# Cameras.net
KiCad netlist of a schematic drawn in Altium Designer
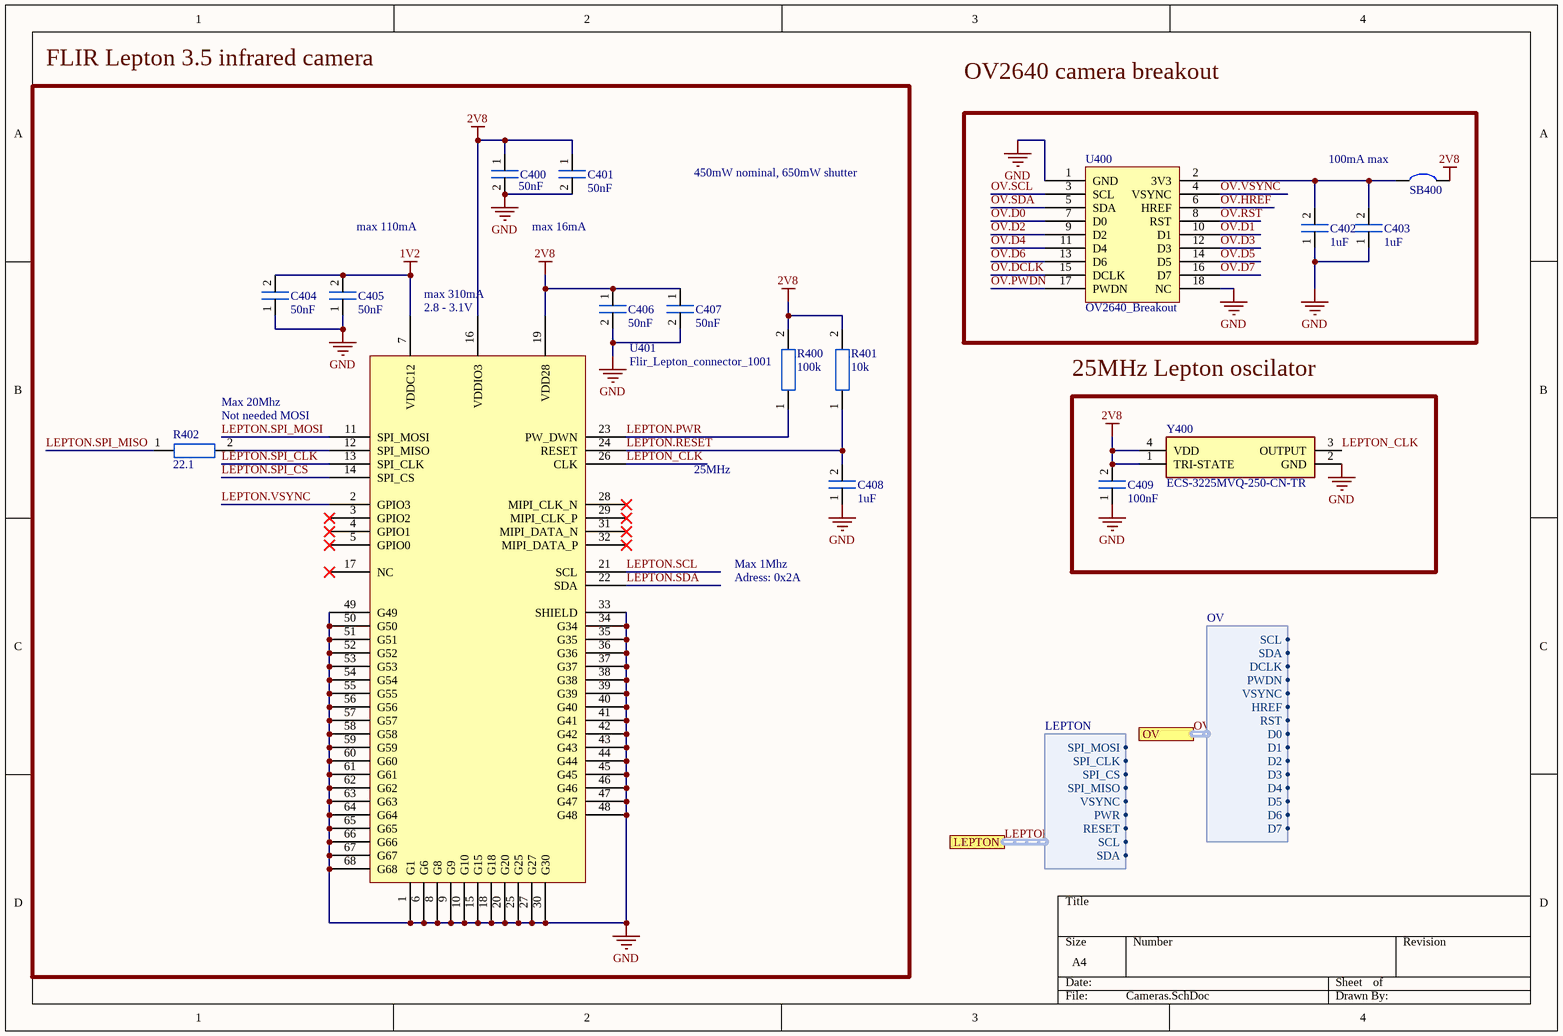
[diagram p0: Cameras.SchDoc]

(export (version "E")
  (design (tool "Eeschema 10.0.6"))
  (components
    (comp (ref "C400")
      (value "50nF")
      (footprint "0402_footprint")
      (description "0402 capacitor")
      (libsource (lib "Schlib1") (part "Capacitor_0402"))
    )
    (comp (ref "C401")
      (value "50nF")
      (footprint "0402_footprint")
      (description "0402 capacitor")
      (libsource (lib "Schlib1") (part "Capacitor_0402"))
    )
    (comp (ref "C402")
      (value "1uF")
      (footprint "0402_footprint")
      (description "0402 capacitor")
      (libsource (lib "Schlib1") (part "Capacitor_0402"))
    )
    (comp (ref "C403")
      (value "1uF")
      (footprint "0402_footprint")
      (description "0402 capacitor")
      (libsource (lib "Schlib1") (part "Capacitor_0402"))
    )
    (comp (ref "C404")
      (value "50nF")
      (footprint "0402_footprint")
      (description "0402 capacitor")
      (libsource (lib "Schlib1") (part "Capacitor_0402"))
    )
    (comp (ref "C405")
      (value "50nF")
      (footprint "0402_footprint")
      (description "0402 capacitor")
      (libsource (lib "Schlib1") (part "Capacitor_0402"))
    )
    (comp (ref "C406")
      (value "50nF")
      (footprint "0402_footprint")
      (description "0402 capacitor")
      (libsource (lib "Schlib1") (part "Capacitor_0402"))
    )
    (comp (ref "C407")
      (value "50nF")
      (footprint "0402_footprint")
      (description "0402 capacitor")
      (libsource (lib "Schlib1") (part "Capacitor_0402"))
    )
    (comp (ref "C408")
      (value "1uF")
      (footprint "0402_footprint")
      (description "0402 capacitor")
      (libsource (lib "Schlib1") (part "Capacitor_0402"))
    )
    (comp (ref "C409")
      (value "100nF")
      (footprint "0402_footprint")
      (description "0402 capacitor")
      (libsource (lib "Schlib1") (part "Capacitor_0402"))
    )
    (comp (ref "R400")
      (value "100k")
      (footprint "0402_footprint")
      (description "0402 resistor")
      (libsource (lib "Schlib1") (part "Resistor_0402"))
    )
    (comp (ref "R401")
      (value "10k")
      (footprint "0402_footprint")
      (description "0402 resistor")
      (libsource (lib "Schlib1") (part "Resistor_0402"))
    )
    (comp (ref "R402")
      (value "22.1")
      (footprint "0402_footprint")
      (description "0402 resistor")
      (libsource (lib "Schlib1") (part "Resistor_0402"))
    )
    (comp (ref "SB400")
      (value "Solder_bridge")
      (footprint "SOLDER_BRIDGE")
      (libsource (lib "Schlib1") (part "Solder_bridge"))
    )
    (comp (ref "U400")
      (value "OV2640_Breakout")
      (footprint "OV2640_BREAKOUT")
      (description "https://www.uctronics.com/download/cam_module/OV2640DS.pdf")
      (libsource (lib "Schlib1") (part "OV2640_Breakout"))
    )
    (comp (ref "U401")
      (value "Flir_Lepton_connector_1001")
      (footprint "105028-1001")
      (libsource (lib "Schlib1") (part "Flir_Lepton_connector_1001"))
    )
    (comp (ref "Y400")
      (value "ECS-3225MVQ-250-CN-TR")
      (footprint "SamacSys:ECS3225MVQ250CNTR")
      (description "25MHz oscilattor")
      (fields (field (name "MOUSER PART NUMBER") "520-3225MVQ-250-CN-T"))
      (libsource (lib "*") (part "ECS-3225MVQ-250-CN-TR"))
    )
  )
  (nets
    (net (code "3") (name "/LEPTON.PWR") (class "Default")
      (node (ref "R400") (pin "1") (pinfunction "1_1") (pintype "passive"))
      (node (ref "U401") (pin "23") (pinfunction "PW_DWN_23") (pintype "passive"))
    )
    (net (code "4") (name "/LEPTON.RESET") (class "Default")
      (node (ref "C408") (pin "2") (pinfunction "2_2") (pintype "passive"))
      (node (ref "R401") (pin "1") (pinfunction "1_1") (pintype "passive"))
      (node (ref "U401") (pin "24") (pinfunction "RESET_24") (pintype "passive"))
    )
    (net (code "5") (name "/LEPTON.SCL") (class "Default")
      (node (ref "U401") (pin "21") (pinfunction "SCL_21") (pintype "passive"))
    )
    (net (code "6") (name "/LEPTON.SDA") (class "Default")
      (node (ref "U401") (pin "22") (pinfunction "SDA_22") (pintype "passive"))
    )
    (net (code "7") (name "/LEPTON.SPI_CLK") (class "Default")
      (node (ref "U401") (pin "13") (pinfunction "SPI_CLK_13") (pintype "passive"))
    )
    (net (code "8") (name "/LEPTON.SPI_CS") (class "Default")
      (node (ref "U401") (pin "14") (pinfunction "SPI_CS_14") (pintype "passive"))
    )
    (net (code "9") (name "/LEPTON.SPI_MISO") (class "Default")
      (node (ref "R402") (pin "1") (pinfunction "1_1") (pintype "passive"))
    )
    (net (code "10") (name "/LEPTON.SPI_MOSI") (class "Default")
      (node (ref "U401") (pin "11") (pinfunction "SPI_MOSI_11") (pintype "passive"))
    )
    (net (code "11") (name "/LEPTON.VSYNC") (class "Default")
      (node (ref "U401") (pin "2") (pinfunction "GPIO3_2") (pintype "passive"))
    )
    (net (code "12") (name "/LEPTON_CLK") (class "Default")
      (node (ref "U401") (pin "26") (pinfunction "CLK_26") (pintype "passive"))
      (node (ref "Y400") (pin "3") (pinfunction "OUTPUT_3") (pintype "passive"))
    )
    (net (code "14") (name "/OV.D0") (class "Default")
      (node (ref "U400") (pin "7") (pinfunction "D0_7") (pintype "passive"))
    )
    (net (code "15") (name "/OV.D1") (class "Default")
      (node (ref "U400") (pin "10") (pinfunction "D1_10") (pintype "passive"))
    )
    (net (code "16") (name "/OV.D2") (class "Default")
      (node (ref "U400") (pin "9") (pinfunction "D2_9") (pintype "passive"))
    )
    (net (code "17") (name "/OV.D3") (class "Default")
      (node (ref "U400") (pin "12") (pinfunction "D3_12") (pintype "passive"))
    )
    (net (code "18") (name "/OV.D4") (class "Default")
      (node (ref "U400") (pin "11") (pinfunction "D4_11") (pintype "passive"))
    )
    (net (code "19") (name "/OV.D5") (class "Default")
      (node (ref "U400") (pin "14") (pinfunction "D5_14") (pintype "passive"))
    )
    (net (code "20") (name "/OV.D6") (class "Default")
      (node (ref "U400") (pin "13") (pinfunction "D6_13") (pintype "passive"))
    )
    (net (code "21") (name "/OV.D7") (class "Default")
      (node (ref "U400") (pin "16") (pinfunction "D7_16") (pintype "passive"))
    )
    (net (code "22") (name "/OV.DCLK") (class "Default")
      (node (ref "U400") (pin "15") (pinfunction "DCLK_15") (pintype "passive"))
    )
    (net (code "23") (name "/OV.HREF") (class "Default")
      (node (ref "U400") (pin "6") (pinfunction "HREF_6") (pintype "passive"))
    )
    (net (code "24") (name "/OV.PWDN") (class "Default")
      (node (ref "U400") (pin "17") (pinfunction "PWDN_17") (pintype "passive"))
    )
    (net (code "25") (name "/OV.RST") (class "Default")
      (node (ref "U400") (pin "8") (pinfunction "RST_8") (pintype "passive"))
    )
    (net (code "26") (name "/OV.SCL") (class "Default")
      (node (ref "U400") (pin "3") (pinfunction "SCL_3") (pintype "passive"))
    )
    (net (code "27") (name "/OV.SDA") (class "Default")
      (node (ref "U400") (pin "5") (pinfunction "SDA_5") (pintype "passive"))
    )
    (net (code "28") (name "/OV.VSYNC") (class "Default")
      (node (ref "U400") (pin "4") (pinfunction "VSYNC_4") (pintype "passive"))
    )
    (net (code "30") (name "1V2") (class "Default")
      (node (ref "C404") (pin "2") (pinfunction "2_2") (pintype "passive"))
      (node (ref "C405") (pin "2") (pinfunction "2_2") (pintype "passive"))
      (node (ref "U401") (pin "7") (pinfunction "VDDC12_7") (pintype "passive"))
    )
    (net (code "31") (name "2V8") (class "Default")
      (node (ref "C400") (pin "1") (pinfunction "1_1") (pintype "passive"))
      (node (ref "C401") (pin "1") (pinfunction "1_1") (pintype "passive"))
      (node (ref "C406") (pin "1") (pinfunction "1_1") (pintype "passive"))
      (node (ref "C407") (pin "1") (pinfunction "1_1") (pintype "passive"))
      (node (ref "C409") (pin "2") (pinfunction "2_2") (pintype "passive"))
      (node (ref "R400") (pin "2") (pinfunction "2_2") (pintype "passive"))
      (node (ref "R401") (pin "2") (pinfunction "2_2") (pintype "passive"))
      (node (ref "SB400") (pin "2") (pinfunction "2_2") (pintype "passive"))
      (node (ref "U401") (pin "16") (pinfunction "VDDIO3_16") (pintype "passive"))
      (node (ref "U401") (pin "19") (pinfunction "VDD28_19") (pintype "passive"))
      (node (ref "Y400") (pin "1") (pinfunction "TRI-STATE_1") (pintype "passive"))
      (node (ref "Y400") (pin "4") (pinfunction "VDD_4") (pintype "passive"))
    )
    (net (code "32") (name "GND") (class "Default")
      (node (ref "C400") (pin "2") (pinfunction "2_2") (pintype "passive"))
      (node (ref "C401") (pin "2") (pinfunction "2_2") (pintype "passive"))
      (node (ref "C402") (pin "1") (pinfunction "1_1") (pintype "passive"))
      (node (ref "C403") (pin "1") (pinfunction "1_1") (pintype "passive"))
      (node (ref "C404") (pin "1") (pinfunction "1_1") (pintype "passive"))
      (node (ref "C405") (pin "1") (pinfunction "1_1") (pintype "passive"))
      (node (ref "C406") (pin "2") (pinfunction "2_2") (pintype "passive"))
      (node (ref "C407") (pin "2") (pinfunction "2_2") (pintype "passive"))
      (node (ref "C408") (pin "1") (pinfunction "1_1") (pintype "passive"))
      (node (ref "C409") (pin "1") (pinfunction "1_1") (pintype "passive"))
      (node (ref "U400") (pin "1") (pinfunction "GND_1") (pintype "passive"))
      (node (ref "U400") (pin "18") (pinfunction "NC_18") (pintype "passive"))
      (node (ref "U401") (pin "1") (pinfunction "G1_1") (pintype "passive"))
      (node (ref "U401") (pin "10") (pinfunction "G10_10") (pintype "passive"))
      (node (ref "U401") (pin "15") (pinfunction "G15_15") (pintype "passive"))
      (node (ref "U401") (pin "18") (pinfunction "G18_18") (pintype "passive"))
      (node (ref "U401") (pin "20") (pinfunction "G20_20") (pintype "passive"))
      (node (ref "U401") (pin "25") (pinfunction "G25_25") (pintype "passive"))
      (node (ref "U401") (pin "27") (pinfunction "G27_27") (pintype "passive"))
      (node (ref "U401") (pin "30") (pinfunction "G30_30") (pintype "passive"))
      (node (ref "U401") (pin "33") (pinfunction "SHIELD_33") (pintype "passive"))
      (node (ref "U401") (pin "34") (pinfunction "G34_34") (pintype "passive"))
      (node (ref "U401") (pin "35") (pinfunction "G35_35") (pintype "passive"))
      (node (ref "U401") (pin "36") (pinfunction "G36_36") (pintype "passive"))
      (node (ref "U401") (pin "37") (pinfunction "G37_37") (pintype "passive"))
      (node (ref "U401") (pin "38") (pinfunction "G38_38") (pintype "passive"))
      (node (ref "U401") (pin "39") (pinfunction "G39_39") (pintype "passive"))
      (node (ref "U401") (pin "40") (pinfunction "G40_40") (pintype "passive"))
      (node (ref "U401") (pin "41") (pinfunction "G41_41") (pintype "passive"))
      (node (ref "U401") (pin "42") (pinfunction "G42_42") (pintype "passive"))
      (node (ref "U401") (pin "43") (pinfunction "G43_43") (pintype "passive"))
      (node (ref "U401") (pin "44") (pinfunction "G44_44") (pintype "passive"))
      (node (ref "U401") (pin "45") (pinfunction "G45_45") (pintype "passive"))
      (node (ref "U401") (pin "46") (pinfunction "G46_46") (pintype "passive"))
      (node (ref "U401") (pin "47") (pinfunction "G47_47") (pintype "passive"))
      (node (ref "U401") (pin "48") (pinfunction "G48_48") (pintype "passive"))
      (node (ref "U401") (pin "49") (pinfunction "G49_49") (pintype "passive"))
      (node (ref "U401") (pin "50") (pinfunction "G50_50") (pintype "passive"))
      (node (ref "U401") (pin "51") (pinfunction "G51_51") (pintype "passive"))
      (node (ref "U401") (pin "52") (pinfunction "G52_52") (pintype "passive"))
      (node (ref "U401") (pin "53") (pinfunction "G53_53") (pintype "passive"))
      (node (ref "U401") (pin "54") (pinfunction "G54_54") (pintype "passive"))
      (node (ref "U401") (pin "55") (pinfunction "G55_55") (pintype "passive"))
      (node (ref "U401") (pin "56") (pinfunction "G56_56") (pintype "passive"))
      (node (ref "U401") (pin "57") (pinfunction "G57_57") (pintype "passive"))
      (node (ref "U401") (pin "58") (pinfunction "G58_58") (pintype "passive"))
      (node (ref "U401") (pin "59") (pinfunction "G59_59") (pintype "passive"))
      (node (ref "U401") (pin "6") (pinfunction "G6_6") (pintype "passive"))
      (node (ref "U401") (pin "60") (pinfunction "G60_60") (pintype "passive"))
      (node (ref "U401") (pin "61") (pinfunction "G61_61") (pintype "passive"))
      (node (ref "U401") (pin "62") (pinfunction "G62_62") (pintype "passive"))
      (node (ref "U401") (pin "63") (pinfunction "G63_63") (pintype "passive"))
      (node (ref "U401") (pin "64") (pinfunction "G64_64") (pintype "passive"))
      (node (ref "U401") (pin "65") (pinfunction "G65_65") (pintype "passive"))
      (node (ref "U401") (pin "66") (pinfunction "G66_66") (pintype "passive"))
      (node (ref "U401") (pin "67") (pinfunction "G67_67") (pintype "passive"))
      (node (ref "U401") (pin "68") (pinfunction "G68_68") (pintype "passive"))
      (node (ref "U401") (pin "8") (pinfunction "G8_8") (pintype "passive"))
      (node (ref "U401") (pin "9") (pinfunction "G9_9") (pintype "passive"))
      (node (ref "Y400") (pin "2") (pinfunction "GND_2") (pintype "passive"))
    )
    (net (code "33") (name "Net-(U400-3V3)") (class "Default")
      (node (ref "C402") (pin "2") (pinfunction "2_2") (pintype "passive"))
      (node (ref "C403") (pin "2") (pinfunction "2_2") (pintype "passive"))
      (node (ref "SB400") (pin "1") (pinfunction "1_1") (pintype "passive"))
      (node (ref "U400") (pin "2") (pinfunction "3V3_2") (pintype "passive"))
    )
    (net (code "34") (name "Net-(U401-SPI_MISO)") (class "Default")
      (node (ref "R402") (pin "2") (pinfunction "2_2") (pintype "passive"))
      (node (ref "U401") (pin "12") (pinfunction "SPI_MISO_12") (pintype "passive"))
    )
    (net (code "35") (name "unconnected-(U401-GPIO0-Pad5)") (class "Default")
      (node (ref "U401") (pin "5") (pinfunction "GPIO0_5") (pintype "passive+no_connect"))
    )
    (net (code "36") (name "unconnected-(U401-GPIO1-Pad4)") (class "Default")
      (node (ref "U401") (pin "4") (pinfunction "GPIO1_4") (pintype "passive+no_connect"))
    )
    (net (code "37") (name "unconnected-(U401-GPIO2-Pad3)") (class "Default")
      (node (ref "U401") (pin "3") (pinfunction "GPIO2_3") (pintype "passive+no_connect"))
    )
    (net (code "38") (name "unconnected-(U401-MIPI_CLK_N-Pad28)") (class "Default")
      (node (ref "U401") (pin "28") (pinfunction "MIPI_CLK_N_28") (pintype "passive+no_connect"))
    )
    (net (code "39") (name "unconnected-(U401-MIPI_CLK_P-Pad29)") (class "Default")
      (node (ref "U401") (pin "29") (pinfunction "MIPI_CLK_P_29") (pintype "passive+no_connect"))
    )
    (net (code "40") (name "unconnected-(U401-MIPI_DATA_N-Pad31)") (class "Default")
      (node (ref "U401") (pin "31") (pinfunction "MIPI_DATA_N_31") (pintype "passive+no_connect"))
    )
    (net (code "41") (name "unconnected-(U401-MIPI_DATA_P-Pad32)") (class "Default")
      (node (ref "U401") (pin "32") (pinfunction "MIPI_DATA_P_32") (pintype "passive+no_connect"))
    )
    (net (code "42") (name "unconnected-(U401-NC-Pad17)") (class "Default")
      (node (ref "U401") (pin "17") (pinfunction "NC_17") (pintype "passive+no_connect"))
    )
  )
)
